# 02_AUDIO_CODEC.net
KiCad netlist of a schematic drawn in Altium Designer
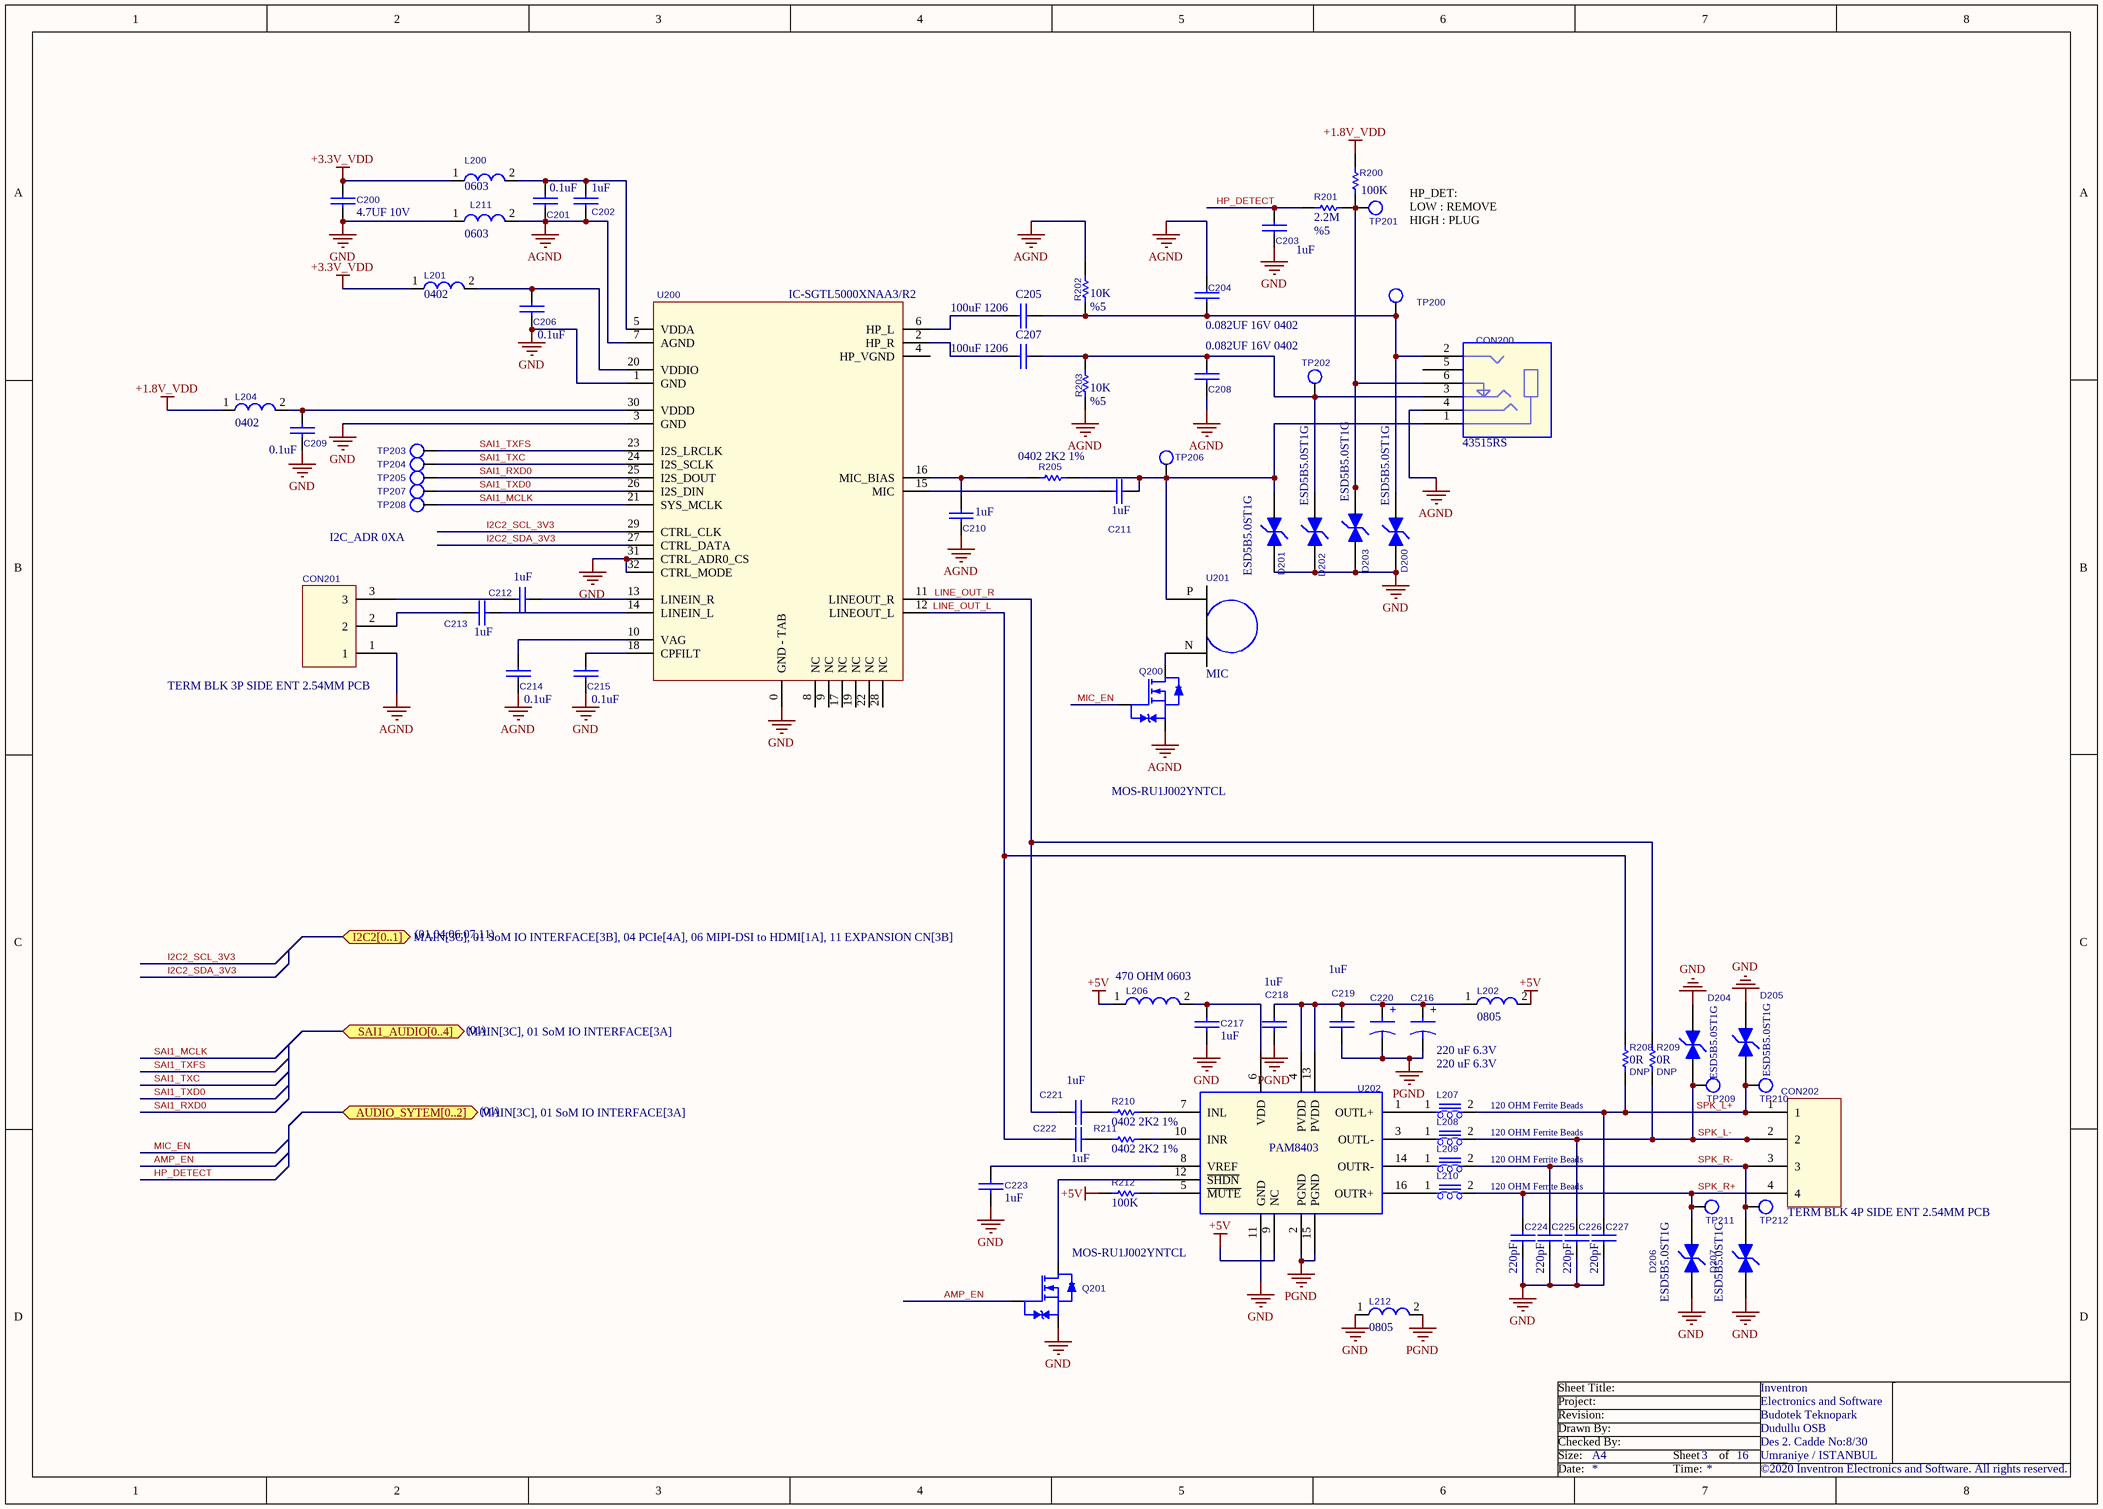
[diagram p0: 02 AUDIO CODEC.SchDoc]

(export (version "E")
  (design (tool "Eeschema 10.0.6"))
  (components
    (comp (ref "C200")
      (value "4.7UF 10V")
      (footprint "0402_CC")
      (description "CAP CER 4.7UF 10V X5R 0402")
      (fields (field (name "CREATED BY") "EE") (field (name "CHECKED BY") "*"))
      (libsource (lib "ARETE_SCH") (part "CAP-CL05A475MP5NRNC"))
    )
    (comp (ref "C201")
      (value "0.1uF")
      (footprint "0402_CC")
      (description "CAP VER 0.1UF 16V X7R 0402")
      (fields (field (name "CREATED BY") "LA") (field (name "CHECKED BY") "*"))
      (libsource (lib "ARETE_SCH") (part "CAP-CL05B104KO5NNNC"))
    )
    (comp (ref "C202")
      (value "1uF")
      (footprint "0603_CC")
      (description "CAP CER 1UF 25V X7R 0603")
      (fields (field (name "CREATED BY") "LA") (field (name "CHECKED BY") "*"))
      (libsource (lib "ARETE_SCH") (part "CAP-CL10B105KA8NNNC"))
    )
    (comp (ref "C203")
      (value "1uF")
      (footprint "0603_CC")
      (description "CAP CER 1UF 25V X7R 0603")
      (fields (field (name "CREATED BY") "LA") (field (name "CHECKED BY") "*"))
      (libsource (lib "ARETE_SCH") (part "CAP-CL10B105KA8NNNC"))
    )
    (comp (ref "C204")
      (value "0.082UF 16V 0402")
      (footprint "0402_CC")
      (description "CAP CER 0.082UF 16V X7R 0402")
      (fields (field (name "CREATED BY") "E.E") (field (name "CHECKED BY") "*"))
      (libsource (lib "ARETE_SCH") (part "CAP-CL05B823KO5NNNC"))
    )
    (comp (ref "C205")
      (value "100uF 1206")
      (footprint "1206")
      (description "CAP CER 100UF 6.3V X5R 1206")
      (fields (field (name "CREATED BY") "EE") (field (name "CHECKED BY") "*"))
      (libsource (lib "ARETE_V2_SCH") (part "CAP-CL31A107MQHNNNE"))
    )
    (comp (ref "C206")
      (value "0.1uF")
      (footprint "0402_CC")
      (description "CAP VER 0.1UF 16V X7R 0402")
      (fields (field (name "CREATED BY") "LA") (field (name "CHECKED BY") "*"))
      (libsource (lib "ARETE_SCH") (part "CAP-CL05B104KO5NNNC"))
    )
    (comp (ref "C207")
      (value "100uF 1206")
      (footprint "1206")
      (description "CAP CER 100UF 6.3V X5R 1206")
      (fields (field (name "CREATED BY") "EE") (field (name "CHECKED BY") "*"))
      (libsource (lib "ARETE_V2_SCH") (part "CAP-CL31A107MQHNNNE"))
    )
    (comp (ref "C208")
      (value "0.082UF 16V 0402")
      (footprint "0402_CC")
      (description "CAP CER 0.082UF 16V X7R 0402")
      (fields (field (name "CREATED BY") "E.E") (field (name "CHECKED BY") "*"))
      (libsource (lib "ARETE_SCH") (part "CAP-CL05B823KO5NNNC"))
    )
    (comp (ref "C209")
      (value "0.1uF")
      (footprint "0402_CC")
      (description "CAP VER 0.1UF 16V X7R 0402")
      (fields (field (name "CREATED BY") "LA") (field (name "CHECKED BY") "*"))
      (libsource (lib "ARETE_SCH") (part "CAP-CL05B104KO5NNNC"))
    )
    (comp (ref "C210")
      (value "1uF")
      (footprint "0603_CC")
      (description "CAP CER 1UF 25V X7R 0603")
      (fields (field (name "CREATED BY") "LA") (field (name "CHECKED BY") "*"))
      (libsource (lib "ARETE_SCH") (part "CAP-CL10B105KA8NNNC"))
    )
    (comp (ref "C211")
      (value "1uF")
      (footprint "0603_CC")
      (description "CAP CER 1UF 25V X7R 0603")
      (fields (field (name "CREATED BY") "LA") (field (name "CHECKED BY") "*"))
      (libsource (lib "ARETE_SCH") (part "CAP-CL10B105KA8NNNC"))
    )
    (comp (ref "C212")
      (value "1uF")
      (footprint "0603_CC")
      (description "CAP CER 1UF 25V X7R 0603")
      (fields (field (name "CREATED BY") "LA") (field (name "CHECKED BY") "*"))
      (libsource (lib "ARETE_SCH") (part "CAP-CL10B105KA8NNNC"))
    )
    (comp (ref "C213")
      (value "1uF")
      (footprint "0603_CC")
      (description "CAP CER 1UF 25V X7R 0603")
      (fields (field (name "CREATED BY") "LA") (field (name "CHECKED BY") "*"))
      (libsource (lib "ARETE_SCH") (part "CAP-CL10B105KA8NNNC"))
    )
    (comp (ref "C214")
      (value "0.1uF")
      (footprint "0402_CC")
      (description "CAP VER 0.1UF 16V X7R 0402")
      (fields (field (name "CREATED BY") "LA") (field (name "CHECKED BY") "*"))
      (libsource (lib "ARETE_SCH") (part "CAP-CL05B104KO5NNNC"))
    )
    (comp (ref "C215")
      (value "0.1uF")
      (footprint "0402_CC")
      (description "CAP VER 0.1UF 16V X7R 0402")
      (fields (field (name "CREATED BY") "LA") (field (name "CHECKED BY") "*"))
      (libsource (lib "ARETE_SCH") (part "CAP-CL05B104KO5NNNC"))
    )
    (comp (ref "C216")
      (value "220 uF 6.3V")
      (footprint "CAP ALUM 6.6x6.6x5.4")
      (description "CAP ALUM 220UF 20% 6.3V SMD")
      (fields (field (name "CREATED BY") "LA") (field (name "CHECKED BY") "*"))
      (libsource (lib "ARETE_L") (part "CAP-EEE-0JA221WP"))
    )
    (comp (ref "C217")
      (value "1uF")
      (footprint "0603_CC")
      (description "CAP CER 1UF 25V X7R 0603")
      (fields (field (name "CREATED BY") "LA") (field (name "CHECKED BY") "*"))
      (libsource (lib "ARETE_SCH") (part "CAP-CL10B105KA8NNNC"))
    )
    (comp (ref "C218")
      (value "1uF")
      (footprint "0603_CC")
      (description "CAP CER 1UF 25V X7R 0603")
      (fields (field (name "CREATED BY") "LA") (field (name "CHECKED BY") "*"))
      (libsource (lib "ARETE_SCH") (part "CAP-CL10B105KA8NNNC"))
    )
    (comp (ref "C219")
      (value "1uF")
      (footprint "0603_CC")
      (description "CAP CER 1UF 25V X7R 0603")
      (fields (field (name "CREATED BY") "LA") (field (name "CHECKED BY") "*"))
      (libsource (lib "ARETE_SCH") (part "CAP-CL10B105KA8NNNC"))
    )
    (comp (ref "C220")
      (value "220 uF 6.3V")
      (footprint "CAP ALUM 6.6x6.6x5.4")
      (description "CAP ALUM 220UF 20% 6.3V SMD")
      (fields (field (name "CREATED BY") "LA") (field (name "CHECKED BY") "*"))
      (libsource (lib "ARETE_L") (part "CAP-EEE-0JA221WP"))
    )
    (comp (ref "C221")
      (value "1uF")
      (footprint "0603_CC")
      (description "CAP CER 1UF 25V X7R 0603")
      (fields (field (name "CREATED BY") "LA") (field (name "CHECKED BY") "*"))
      (libsource (lib "ARETE_SCH") (part "CAP-CL10B105KA8NNNC"))
    )
    (comp (ref "C222")
      (value "1uF")
      (footprint "0603_CC")
      (description "CAP CER 1UF 25V X7R 0603")
      (fields (field (name "CREATED BY") "LA") (field (name "CHECKED BY") "*"))
      (libsource (lib "ARETE_SCH") (part "CAP-CL10B105KA8NNNC"))
    )
    (comp (ref "C223")
      (value "1uF")
      (footprint "0603_CC")
      (description "CAP CER 1UF 25V X7R 0603")
      (fields (field (name "CREATED BY") "LA") (field (name "CHECKED BY") "*"))
      (libsource (lib "ARETE_SCH") (part "CAP-CL10B105KA8NNNC"))
    )
    (comp (ref "C224")
      (value "220pF")
      (footprint "0402_CC")
      (description "220pF ±5% 50V Ceramic Capacitor C0G, NP0 0402 (1005 Metric)")
      (fields (field (name "CREATED BY") "EE") (field (name "CHECKED BY") "*"))
      (libsource (lib "ARETE_SCH") (part "CAP-CL05C221JB5NNNC"))
    )
    (comp (ref "C225")
      (value "220pF")
      (footprint "0402_CC")
      (description "220pF ±5% 50V Ceramic Capacitor C0G, NP0 0402 (1005 Metric)")
      (fields (field (name "CREATED BY") "EE") (field (name "CHECKED BY") "*"))
      (libsource (lib "ARETE_SCH") (part "CAP-CL05C221JB5NNNC"))
    )
    (comp (ref "C226")
      (value "220pF")
      (footprint "0402_CC")
      (description "220pF ±5% 50V Ceramic Capacitor C0G, NP0 0402 (1005 Metric)")
      (fields (field (name "CREATED BY") "EE") (field (name "CHECKED BY") "*"))
      (libsource (lib "ARETE_SCH") (part "CAP-CL05C221JB5NNNC"))
    )
    (comp (ref "C227")
      (value "220pF")
      (footprint "0402_CC")
      (description "220pF ±5% 50V Ceramic Capacitor C0G, NP0 0402 (1005 Metric)")
      (fields (field (name "CREATED BY") "EE") (field (name "CHECKED BY") "*"))
      (libsource (lib "ARETE_SCH") (part "CAP-CL05C221JB5NNNC"))
    )
    (comp (ref "CON200")
      (value "43515RS")
      (footprint "SJ-43515RS-SMT")
      (description "CONN JACK 4COND 3.5MM SMD R/A")
      (fields (field (name "CREATED BY") "LA") (field (name "CHECKED BY") "*"))
      (libsource (lib "ARETE_L") (part "CON-SJ-43515RS-SMT-TR"))
    )
    (comp (ref "CON201")
      (value "TERM BLK 3P SIDE ENT 2.54MM PCB")
      (footprint "OSTVN03A150")
      (description "3 Position Wire to Board Terminal Block Horizontal with Board 0.100\" (2.54mm) Through Hole")
      (fields (field (name "CREATED BY") "E.E") (field (name "CHECKED BY") "*"))
      (libsource (lib "ARETE_SCH") (part "CON-OSTVN03A150"))
    )
    (comp (ref "CON202")
      (value "TERM BLK 4P SIDE ENT 2.54MM PCB")
      (footprint "OSTVN04A150")
      (description "4 Position Wire to Board Terminal Block Horizontal with Board 0.100\" (2.54mm) Through Hole")
      (fields (field (name "CREATED BY") "E.E") (field (name "CHECKED BY") "*"))
      (libsource (lib "ARETE_SCH") (part "CON-OSTVN04A150"))
    )
    (comp (ref "D200")
      (value "ESD5B5.0ST1G")
      (footprint "SOD523 - SZESD")
      (description "VS DIODE 5V SOD523")
      (fields (field (name "CREATED BY") "E.E") (field (name "CHECKED BY") "*"))
      (libsource (lib "ARETE_SCH") (part "DIODE-ESD5B5.0ST1G"))
    )
    (comp (ref "D201")
      (value "ESD5B5.0ST1G")
      (footprint "SOD523 - SZESD")
      (description "VS DIODE 5V SOD523")
      (fields (field (name "CREATED BY") "E.E") (field (name "CHECKED BY") "*"))
      (libsource (lib "ARETE_SCH") (part "DIODE-ESD5B5.0ST1G"))
    )
    (comp (ref "D202")
      (value "ESD5B5.0ST1G")
      (footprint "SOD523 - SZESD")
      (description "VS DIODE 5V SOD523")
      (fields (field (name "CREATED BY") "E.E") (field (name "CHECKED BY") "*"))
      (libsource (lib "ARETE_SCH") (part "DIODE-ESD5B5.0ST1G"))
    )
    (comp (ref "D203")
      (value "ESD5B5.0ST1G")
      (footprint "SOD523 - SZESD")
      (description "VS DIODE 5V SOD523")
      (fields (field (name "CREATED BY") "E.E") (field (name "CHECKED BY") "*"))
      (libsource (lib "ARETE_SCH") (part "DIODE-ESD5B5.0ST1G"))
    )
    (comp (ref "D204")
      (value "ESD5B5.0ST1G")
      (footprint "SOD523 - SZESD")
      (description "VS DIODE 5V SOD523")
      (fields (field (name "CREATED BY") "E.E") (field (name "CHECKED BY") "*"))
      (libsource (lib "ARETE_SCH") (part "DIODE-ESD5B5.0ST1G"))
    )
    (comp (ref "D205")
      (value "ESD5B5.0ST1G")
      (footprint "SOD523 - SZESD")
      (description "VS DIODE 5V SOD523")
      (fields (field (name "CREATED BY") "E.E") (field (name "CHECKED BY") "*"))
      (libsource (lib "ARETE_SCH") (part "DIODE-ESD5B5.0ST1G"))
    )
    (comp (ref "D206")
      (value "ESD5B5.0ST1G")
      (footprint "SOD523 - SZESD")
      (description "VS DIODE 5V SOD523")
      (fields (field (name "CREATED BY") "E.E") (field (name "CHECKED BY") "*"))
      (libsource (lib "ARETE_SCH") (part "DIODE-ESD5B5.0ST1G"))
    )
    (comp (ref "D207")
      (value "ESD5B5.0ST1G")
      (footprint "SOD523 - SZESD")
      (description "VS DIODE 5V SOD523")
      (fields (field (name "CREATED BY") "E.E") (field (name "CHECKED BY") "*"))
      (libsource (lib "ARETE_SCH") (part "DIODE-ESD5B5.0ST1G"))
    )
    (comp (ref "L200")
      (value "0603")
      (footprint "0603_RES")
      (description "0OHM 0603")
      (fields (field (name "CREATED BY") "EE") (field (name "CHECKED BY") "*"))
      (libsource (lib "ARETE_SCH") (part "IND-FERRITE (RES 0 OHM) 0603"))
    )
    (comp (ref "L201")
      (value "0402")
      (footprint "0402_RES")
      (description "0OHM 0402")
      (fields (field (name "CREATED BY") "EE") (field (name "CHECKED BY") "*"))
      (libsource (lib "ARETE_SCH") (part "IND-FERRITE (RES 0 OHM) 0402"))
    )
    (comp (ref "L202")
      (value "0805")
      (footprint "0805")
      (description "0OHM 0805")
      (fields (field (name "CREATED BY") "EE") (field (name "CHECKED BY") "*"))
      (libsource (lib "ARETE_SCH") (part "IND-FERRITE (RES 0 OHM) 0805"))
    )
    (comp (ref "L204")
      (value "0402")
      (footprint "0402_RES")
      (description "0OHM 0402")
      (fields (field (name "CREATED BY") "EE") (field (name "CHECKED BY") "*"))
      (libsource (lib "ARETE_SCH") (part "IND-FERRITE (RES 0 OHM) 0402"))
    )
    (comp (ref "L206")
      (value "470 OHM 0603")
      (footprint "0603_RES")
      (description "- Ferrite Bead 0603 (1608 Metric) 500mA 210mOhm")
      (fields (field (name "CREATED BY") "E.E") (field (name "CHECKED BY") "*"))
      (libsource (lib "ARETE_SCH") (part "IND-BLM18EG471SN1D"))
    )
    (comp (ref "L207")
      (value "120 OHM Ferrite Beads")
      (footprint "0603_RES")
      (description "Ferrite Beads Multi-Layer 120Ohm 25% 100MHz 2A 0.05Ohm DCR 0603 Automotive T/R")
      (fields (field (name "CREATED BY") "E.E") (field (name "CHECKED BY") "*"))
      (libsource (lib "ARETE_SCH") (part "IND-BLM18PG121SH1D"))
    )
    (comp (ref "L208")
      (value "120 OHM Ferrite Beads")
      (footprint "0603_RES")
      (description "Ferrite Beads Multi-Layer 120Ohm 25% 100MHz 2A 0.05Ohm DCR 0603 Automotive T/R")
      (fields (field (name "CREATED BY") "E.E") (field (name "CHECKED BY") "*"))
      (libsource (lib "ARETE_SCH") (part "IND-BLM18PG121SH1D"))
    )
    (comp (ref "L209")
      (value "120 OHM Ferrite Beads")
      (footprint "0603_RES")
      (description "Ferrite Beads Multi-Layer 120Ohm 25% 100MHz 2A 0.05Ohm DCR 0603 Automotive T/R")
      (fields (field (name "CREATED BY") "E.E") (field (name "CHECKED BY") "*"))
      (libsource (lib "ARETE_SCH") (part "IND-BLM18PG121SH1D"))
    )
    (comp (ref "L210")
      (value "120 OHM Ferrite Beads")
      (footprint "0603_RES")
      (description "Ferrite Beads Multi-Layer 120Ohm 25% 100MHz 2A 0.05Ohm DCR 0603 Automotive T/R")
      (fields (field (name "CREATED BY") "E.E") (field (name "CHECKED BY") "*"))
      (libsource (lib "ARETE_SCH") (part "IND-BLM18PG121SH1D"))
    )
    (comp (ref "L211")
      (value "0603")
      (footprint "0603_RES")
      (description "0OHM 0603")
      (fields (field (name "CREATED BY") "EE") (field (name "CHECKED BY") "*"))
      (libsource (lib "ARETE_SCH") (part "IND-FERRITE (RES 0 OHM) 0603"))
    )
    (comp (ref "L212")
      (value "0805")
      (footprint "0805")
      (description "0OHM 0805")
      (fields (field (name "CREATED BY") "EE") (field (name "CHECKED BY") "*"))
      (libsource (lib "ARETE_SCH") (part "IND-FERRITE (RES 0 OHM) 0805"))
    )
    (comp (ref "Q200")
      (value "MOS-RU1J002YNTCL")
      (footprint "SC-85-3/SOT-323FL")
      (description "MOSFET N-CH 50V 0.2A UMT3F")
      (fields (field (name "CREATED BY") "LA") (field (name "CHECKED BY") "*"))
      (libsource (lib "ARETE_SCH") (part "MOS-RU1J002YNTCL"))
    )
    (comp (ref "Q201")
      (value "MOS-RU1J002YNTCL")
      (footprint "SC-85-3/SOT-323FL")
      (description "MOSFET N-CH 50V 0.2A UMT3F")
      (fields (field (name "CREATED BY") "LA") (field (name "CHECKED BY") "*"))
      (libsource (lib "ARETE_SCH") (part "MOS-RU1J002YNTCL"))
    )
    (comp (ref "R200")
      (value "100K")
      (footprint "0402_RES")
      (description "RES 100K OHM 5% 1/16W 0402")
      (fields
        (field (name "TOLERANCE") "%5")
        (field (name "CREATED BY") "LA")
        (field (name "CHECKED BY") "*")
      )
      (libsource (lib "ARETE_SCH") (part "RES-RMCF0402JT100K"))
    )
    (comp (ref "R201")
      (value "2.2M")
      (footprint "0402_RES")
      (description "RES 2.2M OHM 5% 1/16W 0402")
      (fields
        (field (name "TOLERANCE") "%5")
        (field (name "CREATED BY") "LA")
        (field (name "CHECKED BY") "*")
      )
      (libsource (lib "ARETE_SCH") (part "RES-RMCF0402JT2M20"))
    )
    (comp (ref "R202")
      (value "10K")
      (footprint "0402_RES")
      (description "RES 10K OHM 5% 1/16W 0402")
      (fields
        (field (name "TOLERANCE") "%5")
        (field (name "CREATED BY") "LA")
        (field (name "CHECKED BY") "*")
      )
      (libsource (lib "ARETE_SCH") (part "RES-RMCF0402JT10K0"))
    )
    (comp (ref "R203")
      (value "10K")
      (footprint "0402_RES")
      (description "RES 10K OHM 5% 1/16W 0402")
      (fields
        (field (name "TOLERANCE") "%5")
        (field (name "CREATED BY") "LA")
        (field (name "CHECKED BY") "*")
      )
      (libsource (lib "ARETE_SCH") (part "RES-RMCF0402JT10K0"))
    )
    (comp (ref "R205")
      (value "0402 2K2 1%")
      (footprint "0402_RES")
      (fields (field (name "CREATED BY") "E.E") (field (name "CHECKED BY") "*"))
      (libsource (lib "ARETE_SCH") (part "RES-CRGCQ0402F2K2"))
    )
    (comp (ref "R208")
      (value "0R")
      (footprint "0402_RES")
      (description "RES 0 OHM JUMPER 1/16W 0402")
      (fields
        (field (name "ASSY_OPT") "DNP")
        (field (name "CREATED BY") "LA")
        (field (name "CHECKED BY") "*")
      )
      (libsource (lib "ARETE_SCH") (part "RES-RMCF0402ZT0R00"))
    )
    (comp (ref "R209")
      (value "0R")
      (footprint "0402_RES")
      (description "RES 0 OHM JUMPER 1/16W 0402")
      (fields
        (field (name "ASSY_OPT") "DNP")
        (field (name "CREATED BY") "LA")
        (field (name "CHECKED BY") "*")
      )
      (libsource (lib "ARETE_SCH") (part "RES-RMCF0402ZT0R00"))
    )
    (comp (ref "R210")
      (value "0402 2K2 1%")
      (footprint "0402_RES")
      (fields (field (name "CREATED BY") "E.E") (field (name "CHECKED BY") "*"))
      (libsource (lib "ARETE_SCH") (part "RES-CRGCQ0402F2K2"))
    )
    (comp (ref "R211")
      (value "0402 2K2 1%")
      (footprint "0402_RES")
      (fields (field (name "CREATED BY") "E.E") (field (name "CHECKED BY") "*"))
      (libsource (lib "ARETE_SCH") (part "RES-CRGCQ0402F2K2"))
    )
    (comp (ref "R212")
      (value "100K")
      (footprint "0402_RES")
      (description "RES 100K OHM 5% 1/16W 0402")
      (fields
        (field (name "TOLERANCE") "%5")
        (field (name "CREATED BY") "LA")
        (field (name "CHECKED BY") "*")
      )
      (libsource (lib "ARETE_SCH") (part "RES-RMCF0402JT100K"))
    )
    (comp (ref "TP200")
      (value "TEST POINT 15")
      (footprint "testpoint_15")
      (libsource (lib "ARETE_L") (part "TEST POINT 15"))
    )
    (comp (ref "TP201")
      (value "TEST POINT 15")
      (footprint "testpoint_15")
      (libsource (lib "ARETE_L") (part "TEST POINT 15"))
    )
    (comp (ref "TP202")
      (value "TEST POINT 15")
      (footprint "testpoint_15")
      (libsource (lib "ARETE_L") (part "TEST POINT 15"))
    )
    (comp (ref "TP203")
      (value "TEST POINT 15")
      (footprint "testpoint_15")
      (libsource (lib "ARETE_L") (part "TEST POINT 15"))
    )
    (comp (ref "TP204")
      (value "TEST POINT 15")
      (footprint "testpoint_15")
      (libsource (lib "ARETE_L") (part "TEST POINT 15"))
    )
    (comp (ref "TP205")
      (value "TEST POINT 15")
      (footprint "testpoint_15")
      (libsource (lib "ARETE_L") (part "TEST POINT 15"))
    )
    (comp (ref "TP206")
      (value "TEST POINT 15")
      (footprint "testpoint_15")
      (libsource (lib "ARETE_L") (part "TEST POINT 15"))
    )
    (comp (ref "TP207")
      (value "TEST POINT 15")
      (footprint "testpoint_15")
      (libsource (lib "ARETE_L") (part "TEST POINT 15"))
    )
    (comp (ref "TP208")
      (value "TEST POINT 15")
      (footprint "testpoint_15")
      (libsource (lib "ARETE_L") (part "TEST POINT 15"))
    )
    (comp (ref "TP209")
      (value "TEST POINT 15")
      (footprint "testpoint_15")
      (libsource (lib "ARETE_L") (part "TEST POINT 15"))
    )
    (comp (ref "TP210")
      (value "TEST POINT 15")
      (footprint "testpoint_15")
      (libsource (lib "ARETE_L") (part "TEST POINT 15"))
    )
    (comp (ref "TP211")
      (value "TEST POINT 15")
      (footprint "testpoint_15")
      (libsource (lib "ARETE_L") (part "TEST POINT 15"))
    )
    (comp (ref "TP212")
      (value "TEST POINT 15")
      (footprint "testpoint_15")
      (libsource (lib "ARETE_L") (part "TEST POINT 15"))
    )
    (comp (ref "U200")
      (value "IC-SGTL5000XNAA3/R2")
      (footprint "QFN32")
      (description "IC AUDIO CODEC  STEREO SMD QFN32")
      (fields (field (name "CREATED BY") "OKS") (field (name "CHECKED BY") "*"))
      (libsource (lib "ARETE_SCH") (part "IC-SGTL5000XNAA3/R2"))
    )
    (comp (ref "U201")
      (value "MIC")
      (footprint "CMEJ-0415-42-P CON")
      (description "100Hz ~ 10kHz Analog Microphone Electret Condenser Omnidirectional (-42dB ±3dB @ 94dB SPL) PC Pins")
      (fields (field (name "CREATED BY") "E.E") (field (name "CHECKED BY") "*"))
      (libsource (lib "ARETE_SCH") (part "IC-CMEJ-0415-42-P"))
    )
    (comp (ref "U202")
      (value "PAM8403")
      (footprint "SO-16")
      (description "IC AMP AUDIO 3W CLASS D SO16")
      (fields (field (name "CREATED BY") "OKS") (field (name "CHECKED BY") "*"))
      (libsource (lib "ARETE_SCH") (part "IC-PAM8403"))
    )
  )
  (nets
    (net (code "11") (name "+1.8V_VDD") (class "Default")
      (node (ref "L204") (pin "1") (pinfunction "1_1") (pintype "passive"))
      (node (ref "R200") (pin "2") (pinfunction "2_2") (pintype "passive"))
    )
    (net (code "12") (name "+3.3V_VDD") (class "Default")
      (node (ref "C200") (pin "1") (pinfunction "1_1") (pintype "passive"))
      (node (ref "L200") (pin "1") (pinfunction "1_1") (pintype "passive"))
      (node (ref "L201") (pin "1") (pinfunction "1_1") (pintype "passive"))
    )
    (net (code "13") (name "+5V") (class "Default")
      (node (ref "L202") (pin "2") (pinfunction "2_2") (pintype "passive"))
      (node (ref "L206") (pin "1") (pinfunction "1_1") (pintype "passive"))
      (node (ref "R212") (pin "1") (pinfunction "1_1") (pintype "passive"))
      (node (ref "U202") (pin "9") (pinfunction "NC_9") (pintype "passive"))
    )
    (net (code "15") (name "/AMP_EN") (class "Default")
      (node (ref "Q201") (pin "1") (pinfunction "G_1") (pintype "passive"))
    )
    (net (code "17") (name "/HP_DETECT") (class "Default")
      (node (ref "C203") (pin "2") (pinfunction "2_2") (pintype "passive"))
      (node (ref "R201") (pin "1") (pinfunction "1_1") (pintype "passive"))
    )
    (net (code "19") (name "/I2C2_SCL_3V3") (class "Default")
      (node (ref "U200") (pin "29") (pinfunction "CTRL_CLK_29") (pintype "passive"))
    )
    (net (code "20") (name "/I2C2_SDA_3V3") (class "Default")
      (node (ref "U200") (pin "27") (pinfunction "CTRL_DATA_27") (pintype "passive"))
    )
    (net (code "21") (name "/LINE_OUT_L") (class "Default")
      (node (ref "C222") (pin "1") (pinfunction "1_1") (pintype "passive"))
      (node (ref "R208") (pin "2") (pinfunction "2_2") (pintype "passive"))
      (node (ref "U200") (pin "12") (pinfunction "LINEOUT_L_12") (pintype "passive"))
    )
    (net (code "22") (name "/LINE_OUT_R") (class "Default")
      (node (ref "C221") (pin "1") (pinfunction "1_1") (pintype "passive"))
      (node (ref "R209") (pin "2") (pinfunction "2_2") (pintype "passive"))
      (node (ref "U200") (pin "11") (pinfunction "LINEOUT_R_11") (pintype "passive"))
    )
    (net (code "23") (name "/MIC_EN") (class "Default")
      (node (ref "Q200") (pin "1") (pinfunction "G_1") (pintype "passive"))
    )
    (net (code "25") (name "/SAI1_MCLK") (class "Default")
      (node (ref "TP208") (pin "1") (pinfunction "1_1") (pintype "passive"))
      (node (ref "U200") (pin "21") (pinfunction "SYS_MCLK_21") (pintype "passive"))
    )
    (net (code "26") (name "/SAI1_RXD0") (class "Default")
      (node (ref "TP205") (pin "1") (pinfunction "1_1") (pintype "passive"))
      (node (ref "U200") (pin "25") (pinfunction "I2S_DOUT_25") (pintype "passive"))
    )
    (net (code "27") (name "/SAI1_TXC") (class "Default")
      (node (ref "TP204") (pin "1") (pinfunction "1_1") (pintype "passive"))
      (node (ref "U200") (pin "24") (pinfunction "I2S_SCLK_24") (pintype "passive"))
    )
    (net (code "28") (name "/SAI1_TXD0") (class "Default")
      (node (ref "TP207") (pin "1") (pinfunction "1_1") (pintype "passive"))
      (node (ref "U200") (pin "26") (pinfunction "I2S_DIN_26") (pintype "passive"))
    )
    (net (code "29") (name "/SAI1_TXFS") (class "Default")
      (node (ref "TP203") (pin "1") (pinfunction "1_1") (pintype "passive"))
      (node (ref "U200") (pin "23") (pinfunction "I2S_LRCLK_23") (pintype "passive"))
    )
    (net (code "30") (name "/SPK_L+") (class "Default")
      (node (ref "C227") (pin "1") (pinfunction "1_1") (pintype "passive"))
      (node (ref "CON202") (pin "1") (pinfunction "1_1") (pintype "passive"))
      (node (ref "D205") (pin "1") (pinfunction "A_1") (pintype "passive"))
      (node (ref "L207") (pin "2") (pinfunction "2_2") (pintype "passive"))
      (node (ref "R208") (pin "1") (pinfunction "1_1") (pintype "passive"))
      (node (ref "TP210") (pin "1") (pinfunction "1_1") (pintype "passive"))
    )
    (net (code "31") (name "/SPK_L-") (class "Default")
      (node (ref "C226") (pin "1") (pinfunction "1_1") (pintype "passive"))
      (node (ref "CON202") (pin "2") (pinfunction "2_2") (pintype "passive"))
      (node (ref "D204") (pin "1") (pinfunction "A_1") (pintype "passive"))
      (node (ref "L208") (pin "2") (pinfunction "2_2") (pintype "passive"))
      (node (ref "R209") (pin "1") (pinfunction "1_1") (pintype "passive"))
      (node (ref "TP209") (pin "1") (pinfunction "1_1") (pintype "passive"))
    )
    (net (code "32") (name "/SPK_R+") (class "Default")
      (node (ref "C224") (pin "1") (pinfunction "1_1") (pintype "passive"))
      (node (ref "CON202") (pin "4") (pinfunction "4_4") (pintype "passive"))
      (node (ref "D206") (pin "2") (pinfunction "K_2") (pintype "passive"))
      (node (ref "L210") (pin "2") (pinfunction "2_2") (pintype "passive"))
      (node (ref "TP211") (pin "1") (pinfunction "1_1") (pintype "passive"))
    )
    (net (code "33") (name "/SPK_R-") (class "Default")
      (node (ref "C225") (pin "1") (pinfunction "1_1") (pintype "passive"))
      (node (ref "CON202") (pin "3") (pinfunction "3_3") (pintype "passive"))
      (node (ref "D207") (pin "2") (pinfunction "K_2") (pintype "passive"))
      (node (ref "L209") (pin "2") (pinfunction "2_2") (pintype "passive"))
      (node (ref "TP212") (pin "1") (pinfunction "1_1") (pintype "passive"))
    )
    (net (code "34") (name "AGND") (class "Default")
      (node (ref "C201") (pin "2") (pinfunction "2_2") (pintype "passive"))
      (node (ref "C202") (pin "1") (pinfunction "1_1") (pintype "passive"))
      (node (ref "C204") (pin "1") (pinfunction "1_1") (pintype "passive"))
      (node (ref "C208") (pin "2") (pinfunction "2_2") (pintype "passive"))
      (node (ref "C210") (pin "1") (pinfunction "1_1") (pintype "passive"))
      (node (ref "C214") (pin "2") (pinfunction "2_2") (pintype "passive"))
      (node (ref "CON200") (pin "4") (pinfunction "4_4") (pintype "passive"))
      (node (ref "CON201") (pin "1") (pinfunction "1_1") (pintype "passive"))
      (node (ref "L211") (pin "2") (pinfunction "2_2") (pintype "passive"))
      (node (ref "Q200") (pin "2") (pinfunction "S_2") (pintype "passive"))
      (node (ref "R202") (pin "2") (pinfunction "2_2") (pintype "passive"))
      (node (ref "R203") (pin "2") (pinfunction "2_2") (pintype "passive"))
      (node (ref "U200") (pin "7") (pinfunction "AGND_7") (pintype "passive"))
    )
    (net (code "35") (name "GND") (class "Default")
      (node (ref "C200") (pin "2") (pinfunction "2_2") (pintype "passive"))
      (node (ref "C203") (pin "1") (pinfunction "1_1") (pintype "passive"))
      (node (ref "C206") (pin "2") (pinfunction "2_2") (pintype "passive"))
      (node (ref "C209") (pin "2") (pinfunction "2_2") (pintype "passive"))
      (node (ref "C215") (pin "2") (pinfunction "2_2") (pintype "passive"))
      (node (ref "C217") (pin "2") (pinfunction "2_2") (pintype "passive"))
      (node (ref "C223") (pin "2") (pinfunction "2_2") (pintype "passive"))
      (node (ref "C224") (pin "2") (pinfunction "2_2") (pintype "passive"))
      (node (ref "C225") (pin "2") (pinfunction "2_2") (pintype "passive"))
      (node (ref "C226") (pin "2") (pinfunction "2_2") (pintype "passive"))
      (node (ref "C227") (pin "2") (pinfunction "2_2") (pintype "passive"))
      (node (ref "D200") (pin "1") (pinfunction "A_1") (pintype "passive"))
      (node (ref "D201") (pin "1") (pinfunction "A_1") (pintype "passive"))
      (node (ref "D202") (pin "1") (pinfunction "A_1") (pintype "passive"))
      (node (ref "D203") (pin "1") (pinfunction "A_1") (pintype "passive"))
      (node (ref "D204") (pin "2") (pinfunction "K_2") (pintype "passive"))
      (node (ref "D205") (pin "2") (pinfunction "K_2") (pintype "passive"))
      (node (ref "D206") (pin "1") (pinfunction "A_1") (pintype "passive"))
      (node (ref "D207") (pin "1") (pinfunction "A_1") (pintype "passive"))
      (node (ref "L211") (pin "1") (pinfunction "1_1") (pintype "passive"))
      (node (ref "L212") (pin "1") (pinfunction "1_1") (pintype "passive"))
      (node (ref "Q201") (pin "2") (pinfunction "S_2") (pintype "passive"))
      (node (ref "U200") (pin "0") (pinfunction "GND_-_TAB_0") (pintype "passive"))
      (node (ref "U200") (pin "1") (pinfunction "GND_1") (pintype "passive"))
      (node (ref "U200") (pin "3") (pinfunction "GND_3") (pintype "passive"))
      (node (ref "U200") (pin "31") (pinfunction "CTRL_ADR0_CS_31") (pintype "passive"))
      (node (ref "U200") (pin "32") (pinfunction "CTRL_MODE_32") (pintype "passive"))
      (node (ref "U202") (pin "11") (pinfunction "GND_11") (pintype "passive"))
    )
    (net (code "36") (name "Net-(C212-Pad1)") (class "Default")
      (node (ref "C212") (pin "1") (pinfunction "1_1") (pintype "passive"))
      (node (ref "CON201") (pin "3") (pinfunction "3_3") (pintype "passive"))
    )
    (net (code "37") (name "Net-(C213-Pad1)") (class "Default")
      (node (ref "C213") (pin "1") (pinfunction "1_1") (pintype "passive"))
      (node (ref "CON201") (pin "2") (pinfunction "2_2") (pintype "passive"))
    )
    (net (code "38") (name "Net-(C216-Pad1)") (class "Default")
      (node (ref "C216") (pin "1") (pinfunction "1_1") (pintype "passive"))
      (node (ref "C218") (pin "1") (pinfunction "1_1") (pintype "passive"))
      (node (ref "C219") (pin "1") (pinfunction "1_1") (pintype "passive"))
      (node (ref "C220") (pin "1") (pinfunction "1_1") (pintype "passive"))
      (node (ref "L202") (pin "1") (pinfunction "1_1") (pintype "passive"))
      (node (ref "U202") (pin "13") (pinfunction "PVDD_13") (pintype "passive"))
      (node (ref "U202") (pin "4") (pinfunction "PVDD_4") (pintype "passive"))
    )
    (net (code "39") (name "Net-(C221-Pad2)") (class "Default")
      (node (ref "C221") (pin "2") (pinfunction "2_2") (pintype "passive"))
      (node (ref "R210") (pin "1") (pinfunction "1_1") (pintype "passive"))
    )
    (net (code "40") (name "Net-(C222-Pad2)") (class "Default")
      (node (ref "C222") (pin "2") (pinfunction "2_2") (pintype "passive"))
      (node (ref "R211") (pin "1") (pinfunction "1_1") (pintype "passive"))
    )
    (net (code "41") (name "Net-(D200-K)") (class "Default")
      (node (ref "C204") (pin "2") (pinfunction "2_2") (pintype "passive"))
      (node (ref "C205") (pin "2") (pinfunction "2_2") (pintype "passive"))
      (node (ref "CON200") (pin "2") (pinfunction "2_2") (pintype "passive"))
      (node (ref "D200") (pin "2") (pinfunction "K_2") (pintype "passive"))
      (node (ref "R202") (pin "1") (pinfunction "1_1") (pintype "passive"))
      (node (ref "TP200") (pin "1") (pinfunction "1_1") (pintype "passive"))
    )
    (net (code "42") (name "Net-(D201-K)") (class "Default")
      (node (ref "C211") (pin "2") (pinfunction "2_2") (pintype "passive"))
      (node (ref "CON200") (pin "1") (pinfunction "1_1") (pintype "passive"))
      (node (ref "D201") (pin "2") (pinfunction "K_2") (pintype "passive"))
      (node (ref "R205") (pin "2") (pinfunction "2_2") (pintype "passive"))
      (node (ref "TP206") (pin "1") (pinfunction "1_1") (pintype "passive"))
      (node (ref "U201") (pin "P") (pinfunction "P_P") (pintype "passive"))
    )
    (net (code "43") (name "Net-(D202-K)") (class "Default")
      (node (ref "C207") (pin "2") (pinfunction "2_2") (pintype "passive"))
      (node (ref "C208") (pin "1") (pinfunction "1_1") (pintype "passive"))
      (node (ref "CON200") (pin "3") (pinfunction "3_3") (pintype "passive"))
      (node (ref "D202") (pin "2") (pinfunction "K_2") (pintype "passive"))
      (node (ref "R203") (pin "1") (pinfunction "1_1") (pintype "passive"))
      (node (ref "TP202") (pin "1") (pinfunction "1_1") (pintype "passive"))
    )
    (net (code "44") (name "Net-(D203-K)") (class "Default")
      (node (ref "CON200") (pin "6") (pinfunction "6_6") (pintype "passive"))
      (node (ref "D203") (pin "2") (pinfunction "K_2") (pintype "passive"))
      (node (ref "R200") (pin "1") (pinfunction "1_1") (pintype "passive"))
      (node (ref "R201") (pin "2") (pinfunction "2_2") (pintype "passive"))
      (node (ref "TP201") (pin "1") (pinfunction "1_1") (pintype "passive"))
    )
    (net (code "45") (name "Net-(Q200-D)") (class "Default")
      (node (ref "Q200") (pin "3") (pinfunction "D_3") (pintype "passive"))
      (node (ref "U201") (pin "N") (pinfunction "N_N") (pintype "passive"))
    )
    (net (code "46") (name "Net-(Q201-D)") (class "Default")
      (node (ref "Q201") (pin "3") (pinfunction "D_3") (pintype "passive"))
      (node (ref "U202") (pin "12") (pinfunction "~{SHDN}_12") (pintype "passive"))
    )
    (net (code "47") (name "Net-(U200-CPFILT)") (class "Default")
      (node (ref "C215") (pin "1") (pinfunction "1_1") (pintype "passive"))
      (node (ref "U200") (pin "18") (pinfunction "CPFILT_18") (pintype "passive"))
    )
    (net (code "48") (name "Net-(U200-HP_L)") (class "Default")
      (node (ref "C205") (pin "1") (pinfunction "1_1") (pintype "passive"))
      (node (ref "U200") (pin "6") (pinfunction "HP_L_6") (pintype "passive"))
    )
    (net (code "49") (name "Net-(U200-HP_R)") (class "Default")
      (node (ref "C207") (pin "1") (pinfunction "1_1") (pintype "passive"))
      (node (ref "U200") (pin "2") (pinfunction "HP_R_2") (pintype "power_in"))
    )
    (net (code "50") (name "Net-(U200-LINEIN_L)") (class "Default")
      (node (ref "C213") (pin "2") (pinfunction "2_2") (pintype "passive"))
      (node (ref "U200") (pin "14") (pinfunction "LINEIN_L_14") (pintype "passive"))
    )
    (net (code "51") (name "Net-(U200-LINEIN_R)") (class "Default")
      (node (ref "C212") (pin "2") (pinfunction "2_2") (pintype "passive"))
      (node (ref "U200") (pin "13") (pinfunction "LINEIN_R_13") (pintype "passive"))
    )
    (net (code "52") (name "Net-(U200-MIC)") (class "Default")
      (node (ref "C211") (pin "1") (pinfunction "1_1") (pintype "passive"))
      (node (ref "U200") (pin "15") (pinfunction "MIC_15") (pintype "passive"))
    )
    (net (code "53") (name "Net-(U200-MIC_BIAS)") (class "Default")
      (node (ref "C210") (pin "2") (pinfunction "2_2") (pintype "passive"))
      (node (ref "R205") (pin "1") (pinfunction "1_1") (pintype "passive"))
      (node (ref "U200") (pin "16") (pinfunction "MIC_BIAS_16") (pintype "passive"))
    )
    (net (code "54") (name "Net-(U200-VAG)") (class "Default")
      (node (ref "C214") (pin "1") (pinfunction "1_1") (pintype "passive"))
      (node (ref "U200") (pin "10") (pinfunction "VAG_10") (pintype "passive"))
    )
    (net (code "55") (name "Net-(U200-VDDA)") (class "Default")
      (node (ref "C201") (pin "1") (pinfunction "1_1") (pintype "passive"))
      (node (ref "C202") (pin "2") (pinfunction "2_2") (pintype "passive"))
      (node (ref "L200") (pin "2") (pinfunction "2_2") (pintype "passive"))
      (node (ref "U200") (pin "5") (pinfunction "VDDA_5") (pintype "passive"))
    )
    (net (code "56") (name "Net-(U200-VDDD)") (class "Default")
      (node (ref "C209") (pin "1") (pinfunction "1_1") (pintype "passive"))
      (node (ref "L204") (pin "2") (pinfunction "2_2") (pintype "passive"))
      (node (ref "U200") (pin "30") (pinfunction "VDDD_30") (pintype "passive"))
    )
    (net (code "57") (name "Net-(U200-VDDIO)") (class "Default")
      (node (ref "C206") (pin "1") (pinfunction "1_1") (pintype "passive"))
      (node (ref "L201") (pin "2") (pinfunction "2_2") (pintype "passive"))
      (node (ref "U200") (pin "20") (pinfunction "VDDIO_20") (pintype "passive"))
    )
    (net (code "58") (name "Net-(U202-INL)") (class "Default")
      (node (ref "R210") (pin "2") (pinfunction "2_2") (pintype "passive"))
      (node (ref "U202") (pin "7") (pinfunction "INL_7") (pintype "passive"))
    )
    (net (code "59") (name "Net-(U202-INR)") (class "Default")
      (node (ref "R211") (pin "2") (pinfunction "2_2") (pintype "passive"))
      (node (ref "U202") (pin "10") (pinfunction "INR_10") (pintype "passive"))
    )
    (net (code "60") (name "Net-(U202-OUTL+)") (class "Default")
      (node (ref "L207") (pin "1") (pinfunction "1_1") (pintype "passive"))
      (node (ref "U202") (pin "1") (pinfunction "OUTL+_1") (pintype "passive"))
    )
    (net (code "61") (name "Net-(U202-OUTL-)") (class "Default")
      (node (ref "L208") (pin "1") (pinfunction "1_1") (pintype "passive"))
      (node (ref "U202") (pin "3") (pinfunction "OUTL-_3") (pintype "passive"))
    )
    (net (code "62") (name "Net-(U202-OUTR+)") (class "Default")
      (node (ref "L210") (pin "1") (pinfunction "1_1") (pintype "passive"))
      (node (ref "U202") (pin "16") (pinfunction "OUTR+_16") (pintype "passive"))
    )
    (net (code "63") (name "Net-(U202-OUTR-)") (class "Default")
      (node (ref "L209") (pin "1") (pinfunction "1_1") (pintype "passive"))
      (node (ref "U202") (pin "14") (pinfunction "OUTR-_14") (pintype "passive"))
    )
    (net (code "64") (name "Net-(U202-VDD)") (class "Default")
      (node (ref "C217") (pin "1") (pinfunction "1_1") (pintype "passive"))
      (node (ref "L206") (pin "2") (pinfunction "2_2") (pintype "passive"))
      (node (ref "U202") (pin "6") (pinfunction "VDD_6") (pintype "passive"))
    )
    (net (code "65") (name "Net-(U202-VREF)") (class "Default")
      (node (ref "C223") (pin "1") (pinfunction "1_1") (pintype "passive"))
      (node (ref "U202") (pin "8") (pinfunction "VREF_8") (pintype "passive"))
    )
    (net (code "66") (name "Net-(U202-~{MUTE})") (class "Default")
      (node (ref "R212") (pin "2") (pinfunction "2_2") (pintype "passive"))
      (node (ref "U202") (pin "5") (pinfunction "~{MUTE}_5") (pintype "passive"))
    )
    (net (code "67") (name "PGND") (class "Default")
      (node (ref "C216") (pin "2") (pinfunction "2_2") (pintype "passive"))
      (node (ref "C218") (pin "2") (pinfunction "2_2") (pintype "passive"))
      (node (ref "C219") (pin "2") (pinfunction "2_2") (pintype "passive"))
      (node (ref "C220") (pin "2") (pinfunction "2_2") (pintype "passive"))
      (node (ref "L212") (pin "2") (pinfunction "2_2") (pintype "passive"))
      (node (ref "U202") (pin "15") (pinfunction "PGND_15") (pintype "passive"))
      (node (ref "U202") (pin "2") (pinfunction "PGND_2") (pintype "passive"))
    )
    (net (code "68") (name "unconnected-(CON200-Pad5)") (class "Default")
      (node (ref "CON200") (pin "5") (pinfunction "5_5") (pintype "passive"))
    )
    (net (code "69") (name "unconnected-(U200-HP_VGND-Pad4)") (class "Default")
      (node (ref "U200") (pin "4") (pinfunction "HP_VGND_4") (pintype "passive"))
    )
    (net (code "70") (name "unconnected-(U200-NC-Pad8)") (class "Default")
      (node (ref "U200") (pin "8") (pinfunction "NC_8") (pintype "passive"))
    )
    (net (code "71") (name "unconnected-(U200-NC-Pad9)") (class "Default")
      (node (ref "U200") (pin "9") (pinfunction "NC_9") (pintype "passive"))
    )
    (net (code "72") (name "unconnected-(U200-NC-Pad17)") (class "Default")
      (node (ref "U200") (pin "17") (pinfunction "NC_17") (pintype "passive"))
    )
    (net (code "73") (name "unconnected-(U200-NC-Pad19)") (class "Default")
      (node (ref "U200") (pin "19") (pinfunction "NC_19") (pintype "passive"))
    )
    (net (code "74") (name "unconnected-(U200-NC-Pad22)") (class "Default")
      (node (ref "U200") (pin "22") (pinfunction "NC_22") (pintype "passive"))
    )
    (net (code "75") (name "unconnected-(U200-NC-Pad28)") (class "Default")
      (node (ref "U200") (pin "28") (pinfunction "NC_28") (pintype "passive"))
    )
  )
)
